# Power.net
KiCad netlist of a schematic drawn in Altium Designer
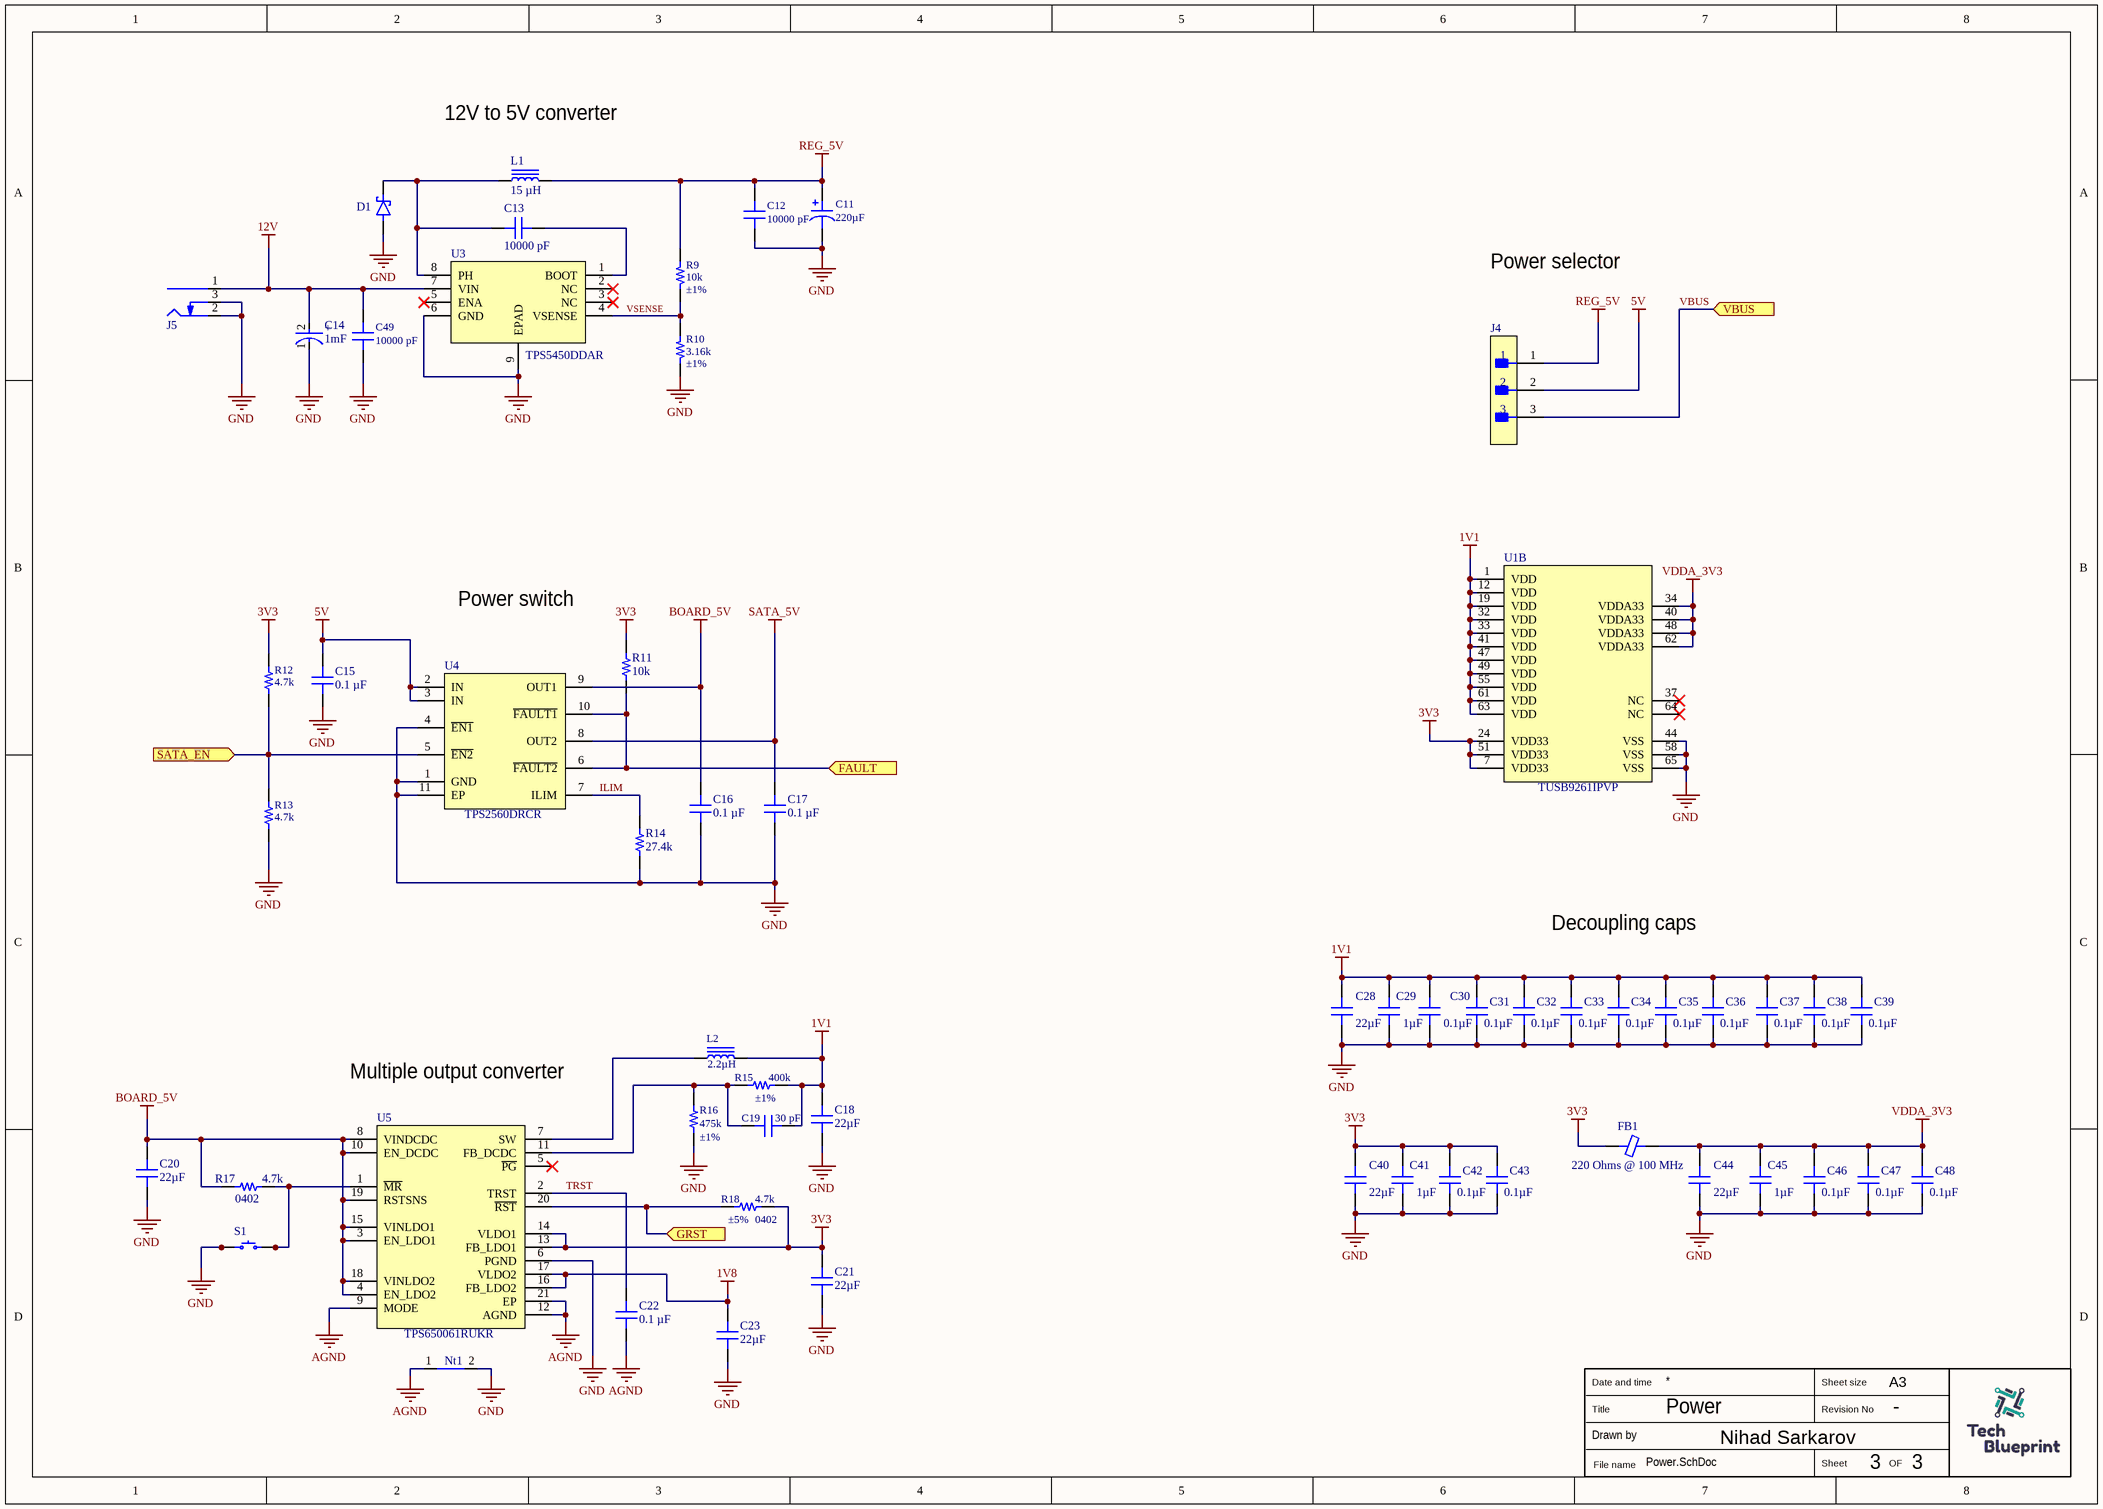
[diagram p0: Power.SchDoc]

(export (version "E")
  (design (tool "Eeschema 10.0.6"))
  (components
    (comp (ref "C11")
      (value "220µF")
      (footprint "CAP ALSMD 8.3MM H10.5MM")
      (description "CAP ALUM 220UF 20% 25V SMD")
      (fields (field (name "PART NUMBER") "UUR1E221MNL6GS") (field (name "MANUFACTURER") "Nichicon"))
      (libsource (lib "Celestial Altium Library - altium_library") (part "Polarised Capacitor"))
    )
    (comp (ref "C12")
      (value "10000 pF")
      (footprint "CAP 0805_2012")
      (description "CAP CER 0805 10NF 100V X7R")
      (fields
        (field (name "PART NUMBER") "C0805X103K1RAC3316")
        (field (name "CAPACITANCE") "10000 pF")
        (field (name "MANUFACTURER") "KEMET")
      )
      (libsource (lib "Celestial Altium Library - altium_library") (part "Capacitor"))
    )
    (comp (ref "C13")
      (value "10000 pF")
      (footprint "CAP 0805_2012")
      (description "CAP CER 0805 10NF 100V X7R")
      (fields
        (field (name "PART NUMBER") "C0805X103K1RAC3316")
        (field (name "CAPACITANCE") "10000 pF")
        (field (name "MANUFACTURER") "KEMET")
      )
      (libsource (lib "Celestial Altium Library - altium_library") (part "Capacitor"))
    )
    (comp (ref "C14")
      (value "EEEFT1C102AP")
      (footprint "FP-FTG-MFG")
      (description "CAP ALUM 1000UF 20% 16V SMD")
      (fields
        (field (name "TOLERANCE") "20%")
        (field (name "CAPACITANCE") "1mF")
        (field (name "VOLTAGE") "16V")
      )
      (libsource (lib "Altium Content Vault") (part "a00bbbee19879c290e62620ae7e47b1"))
    )
    (comp (ref "C15")
      (value "0.1 µF")
      (footprint "CAP 0603_1608")
      (description "CAP CER 0.1UF 50V X7R 0603")
      (fields
        (field (name "PART NUMBER") "CL10B104KB85PND")
        (field (name "CAPACITANCE") "0.1 µF")
        (field (name "MANUFACTURER") "Samsung Electro-Mechanics")
      )
      (libsource (lib "Celestial Altium Library - altium_library") (part "Capacitor"))
    )
    (comp (ref "C16")
      (value "0.1 µF")
      (footprint "CAP 0603_1608")
      (description "CAP CER 0.1UF 50V X7R 0603")
      (fields
        (field (name "PART NUMBER") "CL10B104KB85PND")
        (field (name "CAPACITANCE") "0.1 µF")
        (field (name "MANUFACTURER") "Samsung Electro-Mechanics")
      )
      (libsource (lib "Celestial Altium Library - altium_library") (part "Capacitor"))
    )
    (comp (ref "C17")
      (value "0.1 µF")
      (footprint "CAP 0603_1608")
      (description "CAP CER 0.1UF 50V X7R 0603")
      (fields
        (field (name "PART NUMBER") "CL10B104KB85PND")
        (field (name "CAPACITANCE") "0.1 µF")
        (field (name "MANUFACTURER") "Samsung Electro-Mechanics")
      )
      (libsource (lib "Celestial Altium Library - altium_library") (part "Capacitor"))
    )
    (comp (ref "C18")
      (value "22µF")
      (footprint "CAP 1206_3216 - 1.8MM")
      (description "CAP CER 22UF 16V X5R 1206")
      (fields
        (field (name "PART NUMBER") "1206YD226KAT2A")
        (field (name "CAPACITANCE") "22µF")
        (field (name "MANUFACTURER") "AVX Corporation")
      )
      (libsource (lib "Celestial Altium Library - altium_library") (part "Capacitor"))
    )
    (comp (ref "C19")
      (value "30 pF")
      (footprint "CAP 0402_1005")
      (description "CAP CER 30PF 50V NP0 0402")
      (fields
        (field (name "PART NUMBER") "C0402C300K5GAC7867")
        (field (name "CAPACITANCE") "30 pF")
        (field (name "MANUFACTURER") "KEMET")
      )
      (libsource (lib "Celestial Altium Library - altium_library") (part "Capacitor"))
    )
    (comp (ref "C20")
      (value "22µF")
      (footprint "CAP 1206_3216 - 1.8MM")
      (description "CAP CER 22UF 16V X5R 1206")
      (fields
        (field (name "PART NUMBER") "1206YD226KAT2A")
        (field (name "CAPACITANCE") "22µF")
        (field (name "MANUFACTURER") "AVX Corporation")
      )
      (libsource (lib "Celestial Altium Library - altium_library") (part "Capacitor"))
    )
    (comp (ref "C21")
      (value "22µF")
      (footprint "CAP 1206_3216 - 1.8MM")
      (description "CAP CER 22UF 16V X5R 1206")
      (fields
        (field (name "PART NUMBER") "1206YD226KAT2A")
        (field (name "CAPACITANCE") "22µF")
        (field (name "MANUFACTURER") "AVX Corporation")
      )
      (libsource (lib "Celestial Altium Library - altium_library") (part "Capacitor"))
    )
    (comp (ref "C22")
      (value "0.1 µF")
      (footprint "CAP 0603_1608")
      (description "CAP CER 0.1UF 50V X7R 0603")
      (fields
        (field (name "PART NUMBER") "CL10B104KB85PND")
        (field (name "CAPACITANCE") "0.1 µF")
        (field (name "MANUFACTURER") "Samsung Electro-Mechanics")
      )
      (libsource (lib "Celestial Altium Library - altium_library") (part "Capacitor"))
    )
    (comp (ref "C23")
      (value "22µF")
      (footprint "CAP 1206_3216 - 1.8MM")
      (description "CAP CER 22UF 16V X5R 1206")
      (fields
        (field (name "PART NUMBER") "1206YD226KAT2A")
        (field (name "CAPACITANCE") "22µF")
        (field (name "MANUFACTURER") "AVX Corporation")
      )
      (libsource (lib "Celestial Altium Library - altium_library") (part "Capacitor"))
    )
    (comp (ref "C28")
      (value "22µF")
      (footprint "CAP 1206_3216 - 1.8MM")
      (description "CAP CER 22UF 16V X5R 1206")
      (fields
        (field (name "PART NUMBER") "1206YD226KAT2A")
        (field (name "CAPACITANCE") "22µF")
        (field (name "MANUFACTURER") "AVX Corporation")
      )
      (libsource (lib "Celestial Altium Library - altium_library") (part "Capacitor"))
    )
    (comp (ref "C29")
      (value "1µF")
      (footprint "CAP 0805_2012")
      (description "CAP CER 1UF 10V X7R 0805")
      (fields
        (field (name "PART NUMBER") "MM05ZC105KCZ2A")
        (field (name "CAPACITANCE") "1µF")
        (field (name "MANUFACTURER") "AVX Corporation")
      )
      (libsource (lib "Celestial Altium Library - altium_library") (part "Capacitor"))
    )
    (comp (ref "C30")
      (value "0.1µF")
      (footprint "CAP 0805_2012")
      (description "CAP CER 0.1UF 25V X7R 0805")
      (fields
        (field (name "PART NUMBER") "08053C104KAT4A")
        (field (name "CAPACITANCE") "0.1µF")
        (field (name "MANUFACTURER") "AVX Corporation")
      )
      (libsource (lib "Celestial Altium Library - altium_library") (part "Capacitor"))
    )
    (comp (ref "C31")
      (value "0.1µF")
      (footprint "CAP 0603_1608")
      (description "CAP CER 0.1UF 25V X7R 0603")
      (fields
        (field (name "PART NUMBER") "06033C104K4T4A")
        (field (name "CAPACITANCE") "0.1µF")
        (field (name "MANUFACTURER") "AVX Corporation")
      )
      (libsource (lib "Celestial Altium Library - altium_library") (part "Capacitor"))
    )
    (comp (ref "C32")
      (value "0.1µF")
      (footprint "CAP 0603_1608")
      (description "CAP CER 0.1UF 25V X7R 0603")
      (fields
        (field (name "PART NUMBER") "06033C104K4T4A")
        (field (name "CAPACITANCE") "0.1µF")
        (field (name "MANUFACTURER") "AVX Corporation")
      )
      (libsource (lib "Celestial Altium Library - altium_library") (part "Capacitor"))
    )
    (comp (ref "C33")
      (value "0.1µF")
      (footprint "CAP 0603_1608")
      (description "CAP CER 0.1UF 25V X7R 0603")
      (fields
        (field (name "PART NUMBER") "06033C104K4T4A")
        (field (name "CAPACITANCE") "0.1µF")
        (field (name "MANUFACTURER") "AVX Corporation")
      )
      (libsource (lib "Celestial Altium Library - altium_library") (part "Capacitor"))
    )
    (comp (ref "C34")
      (value "0.1µF")
      (footprint "CAP 0603_1608")
      (description "CAP CER 0.1UF 25V X7R 0603")
      (fields
        (field (name "PART NUMBER") "06033C104K4T4A")
        (field (name "CAPACITANCE") "0.1µF")
        (field (name "MANUFACTURER") "AVX Corporation")
      )
      (libsource (lib "Celestial Altium Library - altium_library") (part "Capacitor"))
    )
    (comp (ref "C35")
      (value "0.1µF")
      (footprint "CAP 0603_1608")
      (description "CAP CER 0.1UF 25V X7R 0603")
      (fields
        (field (name "PART NUMBER") "06033C104K4T4A")
        (field (name "CAPACITANCE") "0.1µF")
        (field (name "MANUFACTURER") "AVX Corporation")
      )
      (libsource (lib "Celestial Altium Library - altium_library") (part "Capacitor"))
    )
    (comp (ref "C36")
      (value "0.1µF")
      (footprint "CAP 0603_1608")
      (description "CAP CER 0.1UF 25V X7R 0603")
      (fields
        (field (name "PART NUMBER") "06033C104K4T4A")
        (field (name "CAPACITANCE") "0.1µF")
        (field (name "MANUFACTURER") "AVX Corporation")
      )
      (libsource (lib "Celestial Altium Library - altium_library") (part "Capacitor"))
    )
    (comp (ref "C37")
      (value "0.1µF")
      (footprint "CAP 0603_1608")
      (description "CAP CER 0.1UF 25V X7R 0603")
      (fields
        (field (name "PART NUMBER") "06033C104K4T4A")
        (field (name "CAPACITANCE") "0.1µF")
        (field (name "MANUFACTURER") "AVX Corporation")
      )
      (libsource (lib "Celestial Altium Library - altium_library") (part "Capacitor"))
    )
    (comp (ref "C38")
      (value "0.1µF")
      (footprint "CAP 0603_1608")
      (description "CAP CER 0.1UF 25V X7R 0603")
      (fields
        (field (name "PART NUMBER") "06033C104K4T4A")
        (field (name "CAPACITANCE") "0.1µF")
        (field (name "MANUFACTURER") "AVX Corporation")
      )
      (libsource (lib "Celestial Altium Library - altium_library") (part "Capacitor"))
    )
    (comp (ref "C39")
      (value "0.1µF")
      (footprint "CAP 0603_1608")
      (description "CAP CER 0.1UF 25V X7R 0603")
      (fields
        (field (name "PART NUMBER") "06033C104K4T4A")
        (field (name "CAPACITANCE") "0.1µF")
        (field (name "MANUFACTURER") "AVX Corporation")
      )
      (libsource (lib "Celestial Altium Library - altium_library") (part "Capacitor"))
    )
    (comp (ref "C40")
      (value "22µF")
      (footprint "CAP 1206_3216 - 1.8MM")
      (description "CAP CER 22UF 16V X5R 1206")
      (fields
        (field (name "PART NUMBER") "1206YD226KAT2A")
        (field (name "CAPACITANCE") "22µF")
        (field (name "MANUFACTURER") "AVX Corporation")
      )
      (libsource (lib "Celestial Altium Library - altium_library") (part "Capacitor"))
    )
    (comp (ref "C41")
      (value "1µF")
      (footprint "CAP 0805_2012")
      (description "CAP CER 1UF 10V X7R 0805")
      (fields
        (field (name "PART NUMBER") "MM05ZC105KCZ2A")
        (field (name "CAPACITANCE") "1µF")
        (field (name "MANUFACTURER") "AVX Corporation")
      )
      (libsource (lib "Celestial Altium Library - altium_library") (part "Capacitor"))
    )
    (comp (ref "C42")
      (value "0.1µF")
      (footprint "CAP 0603_1608")
      (description "CAP CER 0.1UF 25V X7R 0603")
      (fields
        (field (name "PART NUMBER") "06033C104K4T4A")
        (field (name "CAPACITANCE") "0.1µF")
        (field (name "MANUFACTURER") "AVX Corporation")
      )
      (libsource (lib "Celestial Altium Library - altium_library") (part "Capacitor"))
    )
    (comp (ref "C43")
      (value "0.1µF")
      (footprint "CAP 0603_1608")
      (description "CAP CER 0.1UF 25V X7R 0603")
      (fields
        (field (name "PART NUMBER") "06033C104K4T4A")
        (field (name "CAPACITANCE") "0.1µF")
        (field (name "MANUFACTURER") "AVX Corporation")
      )
      (libsource (lib "Celestial Altium Library - altium_library") (part "Capacitor"))
    )
    (comp (ref "C44")
      (value "22µF")
      (footprint "CAP 1206_3216 - 1.8MM")
      (description "CAP CER 22UF 16V X5R 1206")
      (fields
        (field (name "PART NUMBER") "1206YD226KAT2A")
        (field (name "CAPACITANCE") "22µF")
        (field (name "MANUFACTURER") "AVX Corporation")
      )
      (libsource (lib "Celestial Altium Library - altium_library") (part "Capacitor"))
    )
    (comp (ref "C45")
      (value "1µF")
      (footprint "CAP 0805_2012")
      (description "CAP CER 1UF 10V X7R 0805")
      (fields
        (field (name "PART NUMBER") "MM05ZC105KCZ2A")
        (field (name "CAPACITANCE") "1µF")
        (field (name "MANUFACTURER") "AVX Corporation")
      )
      (libsource (lib "Celestial Altium Library - altium_library") (part "Capacitor"))
    )
    (comp (ref "C46")
      (value "0.1µF")
      (footprint "CAP 0603_1608")
      (description "CAP CER 0.1UF 25V X7R 0603")
      (fields
        (field (name "PART NUMBER") "06033C104K4T4A")
        (field (name "CAPACITANCE") "0.1µF")
        (field (name "MANUFACTURER") "AVX Corporation")
      )
      (libsource (lib "Celestial Altium Library - altium_library") (part "Capacitor"))
    )
    (comp (ref "C47")
      (value "0.1µF")
      (footprint "CAP 0603_1608")
      (description "CAP CER 0.1UF 25V X7R 0603")
      (fields
        (field (name "PART NUMBER") "06033C104K4T4A")
        (field (name "CAPACITANCE") "0.1µF")
        (field (name "MANUFACTURER") "AVX Corporation")
      )
      (libsource (lib "Celestial Altium Library - altium_library") (part "Capacitor"))
    )
    (comp (ref "C48")
      (value "0.1µF")
      (footprint "CAP 0603_1608")
      (description "CAP CER 0.1UF 25V X7R 0603")
      (fields
        (field (name "PART NUMBER") "06033C104K4T4A")
        (field (name "CAPACITANCE") "0.1µF")
        (field (name "MANUFACTURER") "AVX Corporation")
      )
      (libsource (lib "Celestial Altium Library - altium_library") (part "Capacitor"))
    )
    (comp (ref "C49")
      (value "10000 pF")
      (footprint "CAP 0805_2012")
      (description "CAP CER 0805 10NF 100V X7R")
      (fields
        (field (name "PART NUMBER") "C0805X103K1RAC3316")
        (field (name "CAPACITANCE") "10000 pF")
        (field (name "MANUFACTURER") "KEMET")
      )
      (libsource (lib "Celestial Altium Library - altium_library") (part "Capacitor"))
    )
    (comp (ref "D1")
      (value "MBRS540T3G")
      (footprint "MBRS540T3G:DIOM7959X261N")
      (fields (field (name "MF") "{'manufacturer': u'ON Semiconductor'}"))
      (libsource (lib "USB to SATA") (part "MBRS540T3G"))
    )
    (comp (ref "FB1")
      (value "220 Ohms @ 100 MHz")
      (footprint "FER 0603_1608")
      (description "POWER LINE HIGH IMPEDANCE FERRIT")
      (fields (field (name "PART NUMBER") "Z0603C221BPWZT") (field (name "MANUFACTURER") "KEMET"))
      (libsource (lib "Celestial Altium Library - altium_library") (part "Ferrite Chip"))
    )
    (comp (ref "J4")
      (value "87224-3")
      (footprint "FP-87224-3-MFG")
      (description "CONN HEADER VERT 3POS 2.54MM")
      (libsource (lib "USB to SATA") (part "CMP-2000-05697-2"))
    )
    (comp (ref "J5")
      (value "PJ-002AH-SMT-TR")
      (footprint "CUI PJ-002AH-SMT-TR")
      (description "CONN PWR JACK 2X5.5MM SOLDER")
      (fields (field (name "MANUFACTURER") "CUI Devices"))
      (libsource (lib "Celestial Altium Library - altium_library") (part "Barrel Connector"))
    )
    (comp (ref "L1")
      (value "15 µH")
      (footprint "BOURNS SRR1280")
      (description "FIXED IND 15UH 5.2A 28.5MOHM SMD")
      (fields (field (name "PART NUMBER") "SRR1280-150M") (field (name "MANUFACTURER") "Bourns Inc."))
      (libsource (lib "") (part "Inductor_1"))
    )
    (comp (ref "L2")
      (value "2.2µH")
      (footprint "IND 1008_2520")
      (description "FIXED IND 2.2UH 700MA 150 MOHM")
      (fields (field (name "PART NUMBER") "CKP2520V2R2M-T") (field (name "MANUFACTURER") "Taiyo Yuden"))
      (libsource (lib "Celestial Altium Library - altium_library") (part "Inductor"))
    )
    (comp (ref "Nt1")
      (value "Net tie")
      (footprint "Net tie")
      (description "Net tie SMD")
      (libsource (lib "USB to SATA") (part "Net tie"))
    )
    (comp (ref "R9")
      (value "10k")
      (footprint "YAGEO RES 0603_1608")
      (description "RES SMD 10K OHM 1% 1/10W 0603")
      (fields
        (field (name "PART NUMBER") "RT0603FRE0710KL")
        (field (name "MANUFACTURER") "Yageo")
        (field (name "TOLERANCE") "±1%")
      )
      (libsource (lib "Celestial Altium Library - altium_library") (part "Resistor"))
    )
    (comp (ref "R10")
      (value "3.16k")
      (footprint "RES 0603_1608")
      (description "RES SMD 3.16K OHM 1% 1/10W 0603")
      (fields
        (field (name "PART NUMBER") "CR0603-FX-3161ELF")
        (field (name "MANUFACTURER") "Bourns Inc.")
        (field (name "TOLERANCE") "±1%")
      )
      (libsource (lib "Celestial Altium Library - altium_library") (part "Resistor"))
    )
    (comp (ref "R11")
      (value "10k")
      (footprint "YAGEO RES 0402_1005")
      (description "RES SMD 10K OHM 5% 1/16W 0402")
      (fields (field (name "PART NUMBER") "AC0402JR-0710KL") (field (name "MANUFACTURER") "Yageo"))
      (libsource (lib "Celestial Altium Library - altium_library") (part "Resistor"))
    )
    (comp (ref "R12")
      (value "4.7k")
      (footprint "RES 0603_1608")
      (description "RES 4.7K OHM 5% 1/10W 0603")
      (fields
        (field (name "PART NUMBER") "RMCF0603JT4K70")
        (field (name "MANUFACTURER") "Stackpole Electronics Inc")
      )
      (libsource (lib "Celestial Altium Library - altium_library") (part "Resistor"))
    )
    (comp (ref "R13")
      (value "4.7k")
      (footprint "RES 0603_1608")
      (description "RES 4.7K OHM 5% 1/10W 0603")
      (fields
        (field (name "PART NUMBER") "RMCF0603JT4K70")
        (field (name "MANUFACTURER") "Stackpole Electronics Inc")
      )
      (libsource (lib "Celestial Altium Library - altium_library") (part "Resistor"))
    )
    (comp (ref "R14")
      (value "27.4k")
      (footprint "RES 0402_1005")
      (description "RES SMD 27.4K OHM 1% 1/10W 0402")
      (fields
        (field (name "PART NUMBER") "ERJ-2RKF2742X")
        (field (name "MANUFACTURER") "Panasonic Electronic Components")
      )
      (libsource (lib "Celestial Altium Library - altium_library") (part "Resistor"))
    )
    (comp (ref "R15")
      (value "400k")
      (footprint "KOA RES RK73 RN73 0402_1005")
      (description "RES 400K OHM 1% 1/10W 0402")
      (fields
        (field (name "PART NUMBER") "RK73H1ETTP4123F")
        (field (name "MANUFACTURER") "KOA Speer Electronics, Inc.")
        (field (name "TOLERANCE") "±1%")
      )
      (libsource (lib "Celestial Altium Library - altium_library") (part "Resistor"))
    )
    (comp (ref "R16")
      (value "475k")
      (footprint "RES 0402_1005")
      (description "RES 475K OHM 1% 1/16W 0402")
      (fields
        (field (name "PART NUMBER") "RMCF0402FT475K")
        (field (name "MANUFACTURER") "Stackpole Electronics Inc")
        (field (name "TOLERANCE") "±1%")
      )
      (libsource (lib "Celestial Altium Library - altium_library") (part "Resistor"))
    )
    (comp (ref "R17")
      (value "4.7k")
      (footprint "YAGEO RES 0402_1005")
      (description "RES SMD 4.7K OHM 5% 1/16W 0402")
      (fields
        (field (name "PART NUMBER") "AC0402JR-074K7L")
        (field (name "MANUFACTURER") "Yageo")
        (field (name "SUPPLIER DEVICE PACKAGE") "0402")
      )
      (libsource (lib "Celestial Altium Library - altium_library") (part "Resistor"))
    )
    (comp (ref "R18")
      (value "4.7k")
      (footprint "YAGEO RES 0402_1005")
      (description "RES SMD 4.7K OHM 5% 1/16W 0402")
      (fields
        (field (name "PART NUMBER") "AC0402JR-074K7L")
        (field (name "MANUFACTURER") "Yageo")
        (field (name "SUPPLIER DEVICE PACKAGE") "0402")
        (field (name "TOLERANCE") "±5%")
      )
      (libsource (lib "Celestial Altium Library - altium_library") (part "Resistor"))
    )
    (comp (ref "S1")
      (value "PTS645SM43SMTR92 LFS")
      (footprint "C&K PTS645")
      (description "SWITCH TACTILE SPST-NO 0.05A 12V")
      (fields (field (name "MANUFACTURER") "C&K"))
      (libsource (lib "Celestial Altium Library - altium_library") (part "SPST-NO 4 PIN"))
    )
    (comp (ref "U1")
      (value "TUSB9261IPVP")
      (footprint "FP-PVP0064A-IPC_A")
      (description "HDD, CD, DVD Drive Interface 64-HTQFP (7x7)")
      (fields
        (field (name "MANUFACTURER") "Texas Instruments")
        (field (name "DIGIKEY PART NUMBER") "296-35545-ND")
      )
      (libsource (lib "USB to SATA") (part "TUSB9261IPVP"))
    )
    (comp (ref "U3")
      (value "TPS5450DDAR")
      (footprint "FP-DDA0008J-IPC_A")
      (description "IC REG BUCK ADJUSTABLE 5A 8SOPWR")
      (fields
        (field (name "MANUFACTURER") "Texas Instruments")
        (field (name "OCTOPART") "https://octopart.com/tps5450ddar-texas+instruments-7105511")
      )
      (libsource (lib "USB to SATA") (part "CMP-04918-000100-1"))
    )
    (comp (ref "U4")
      (value "TPS2560DRCR")
      (footprint "FP-DRC0010J-IPC_A")
      (description "IC PWR SWITCH N-CHAN 1:2 10VSON")
      (libsource (lib "USB to SATA") (part "CMP-0337-00200-3"))
    )
    (comp (ref "U5")
      (value "TPS650061RUKR")
      (footprint "RUK0020B")
      (fields (field (name "MANUFACTURER") "Texas Instruments"))
      (libsource (lib "USB to SATA") (part "CMP-1518-00013-2"))
    )
  )
  (nets
    (net (code "1") (name "/FAULT") (class "Default")
      (node (ref "R11") (pin "1") (pinfunction "1_1") (pintype "passive"))
      (node (ref "U4") (pin "10") (pinfunction "~{FAULT1}_10") (pintype "passive"))
      (node (ref "U4") (pin "6") (pinfunction "~{FAULT2}_6") (pintype "passive"))
    )
    (net (code "2") (name "/GRST") (class "Default")
      (node (ref "R18") (pin "1") (pinfunction "1_1") (pintype "passive"))
      (node (ref "U5") (pin "20") (pinfunction "~{RST}_20") (pintype "passive"))
    )
    (net (code "3") (name "/ILIM") (class "Default")
      (node (ref "R14") (pin "2") (pinfunction "2_2") (pintype "passive"))
      (node (ref "U4") (pin "7") (pinfunction "ILIM_7") (pintype "passive"))
    )
    (net (code "4") (name "/SATA_EN") (class "Default")
      (node (ref "R12") (pin "1") (pinfunction "1_1") (pintype "passive"))
      (node (ref "R13") (pin "2") (pinfunction "2_2") (pintype "passive"))
      (node (ref "U4") (pin "5") (pinfunction "~{EN2}_5") (pintype "passive"))
    )
    (net (code "5") (name "/TRST") (class "Default")
      (node (ref "C22") (pin "2") (pinfunction "2_2") (pintype "passive"))
      (node (ref "U5") (pin "2") (pinfunction "TRST_2") (pintype "passive"))
    )
    (net (code "6") (name "/VBUS") (class "Default")
      (node (ref "J4") (pin "3") (pinfunction "3_3") (pintype "passive"))
    )
    (net (code "7") (name "/VSENSE") (class "Default")
      (node (ref "R10") (pin "2") (pinfunction "2_2") (pintype "passive"))
      (node (ref "R9") (pin "1") (pinfunction "1_1") (pintype "passive"))
      (node (ref "U3") (pin "4") (pinfunction "VSENSE_4") (pintype "passive"))
    )
    (net (code "8") (name "1V1") (class "Default")
      (node (ref "C18") (pin "2") (pinfunction "2_2") (pintype "passive"))
      (node (ref "C19") (pin "2") (pinfunction "2_2") (pintype "passive"))
      (node (ref "C28") (pin "2") (pinfunction "2_2") (pintype "passive"))
      (node (ref "C29") (pin "2") (pinfunction "2_2") (pintype "passive"))
      (node (ref "C30") (pin "2") (pinfunction "2_2") (pintype "passive"))
      (node (ref "C31") (pin "2") (pinfunction "2_2") (pintype "passive"))
      (node (ref "C32") (pin "2") (pinfunction "2_2") (pintype "passive"))
      (node (ref "C33") (pin "2") (pinfunction "2_2") (pintype "passive"))
      (node (ref "C34") (pin "2") (pinfunction "2_2") (pintype "passive"))
      (node (ref "C35") (pin "2") (pinfunction "2_2") (pintype "passive"))
      (node (ref "C36") (pin "2") (pinfunction "2_2") (pintype "passive"))
      (node (ref "C37") (pin "2") (pinfunction "2_2") (pintype "passive"))
      (node (ref "C38") (pin "2") (pinfunction "2_2") (pintype "passive"))
      (node (ref "C39") (pin "2") (pinfunction "2_2") (pintype "passive"))
      (node (ref "L2") (pin "2") (pinfunction "2_2") (pintype "passive"))
      (node (ref "R15") (pin "2") (pinfunction "2_2") (pintype "passive"))
      (node (ref "U1") (pin "1") (pinfunction "VDD_1") (pintype "passive"))
      (node (ref "U1") (pin "12") (pinfunction "VDD_12") (pintype "passive"))
      (node (ref "U1") (pin "19") (pinfunction "VDD_19") (pintype "passive"))
      (node (ref "U1") (pin "32") (pinfunction "VDD_32") (pintype "passive"))
      (node (ref "U1") (pin "33") (pinfunction "VDD_33") (pintype "passive"))
      (node (ref "U1") (pin "41") (pinfunction "VDD_41") (pintype "passive"))
      (node (ref "U1") (pin "47") (pinfunction "VDD_47") (pintype "passive"))
      (node (ref "U1") (pin "49") (pinfunction "VDD_49") (pintype "passive"))
      (node (ref "U1") (pin "55") (pinfunction "VDD_55") (pintype "passive"))
      (node (ref "U1") (pin "61") (pinfunction "VDD_61") (pintype "passive"))
      (node (ref "U1") (pin "63") (pinfunction "VDD_63") (pintype "passive"))
    )
    (net (code "9") (name "1V8") (class "Default")
      (node (ref "C23") (pin "2") (pinfunction "2_2") (pintype "passive"))
      (node (ref "U5") (pin "16") (pinfunction "FB_LDO2_16") (pintype "passive"))
      (node (ref "U5") (pin "17") (pinfunction "VLDO2_17") (pintype "passive"))
    )
    (net (code "10") (name "3V3") (class "Default")
      (node (ref "C21") (pin "2") (pinfunction "2_2") (pintype "passive"))
      (node (ref "C40") (pin "2") (pinfunction "2_2") (pintype "passive"))
      (node (ref "C41") (pin "2") (pinfunction "2_2") (pintype "passive"))
      (node (ref "C42") (pin "2") (pinfunction "2_2") (pintype "passive"))
      (node (ref "C43") (pin "2") (pinfunction "2_2") (pintype "passive"))
      (node (ref "FB1") (pin "1") (pinfunction "1_1") (pintype "passive"))
      (node (ref "R11") (pin "2") (pinfunction "2_2") (pintype "passive"))
      (node (ref "R12") (pin "2") (pinfunction "2_2") (pintype "passive"))
      (node (ref "R18") (pin "2") (pinfunction "2_2") (pintype "passive"))
      (node (ref "U1") (pin "24") (pinfunction "VDD33_24") (pintype "passive"))
      (node (ref "U1") (pin "51") (pinfunction "VDD33_51") (pintype "passive"))
      (node (ref "U1") (pin "7") (pinfunction "VDD33_7") (pintype "passive"))
      (node (ref "U5") (pin "13") (pinfunction "FB_LDO1_13") (pintype "passive"))
      (node (ref "U5") (pin "14") (pinfunction "VLDO1_14") (pintype "passive"))
    )
    (net (code "11") (name "5V") (class "Default")
      (node (ref "C15") (pin "2") (pinfunction "2_2") (pintype "passive"))
      (node (ref "J4") (pin "2") (pinfunction "2_2") (pintype "passive"))
      (node (ref "U4") (pin "2") (pinfunction "IN_2") (pintype "power_in"))
      (node (ref "U4") (pin "3") (pinfunction "IN_3") (pintype "power_in"))
    )
    (net (code "12") (name "12V") (class "Default")
      (node (ref "C14") (pin "2") (pinfunction "A_2") (pintype "passive"))
      (node (ref "C49") (pin "2") (pinfunction "2_2") (pintype "passive"))
      (node (ref "J5") (pin "1") (pinfunction "Centre_1") (pintype "passive"))
      (node (ref "U3") (pin "7") (pinfunction "VIN_7") (pintype "passive"))
    )
    (net (code "13") (name "AGND") (class "Default")
      (node (ref "C22") (pin "1") (pinfunction "1_1") (pintype "passive"))
      (node (ref "Nt1") (pin "1") (pinfunction "1_1") (pintype "passive"))
      (node (ref "U5") (pin "12") (pinfunction "AGND_12") (pintype "passive"))
      (node (ref "U5") (pin "21") (pinfunction "EP_21") (pintype "passive"))
      (node (ref "U5") (pin "9") (pinfunction "MODE_9") (pintype "passive"))
    )
    (net (code "14") (name "BOARD_5V") (class "Default")
      (node (ref "C16") (pin "2") (pinfunction "2_2") (pintype "passive"))
      (node (ref "C20") (pin "2") (pinfunction "2_2") (pintype "passive"))
      (node (ref "R17") (pin "1") (pinfunction "1_1") (pintype "passive"))
      (node (ref "U4") (pin "9") (pinfunction "OUT1_9") (pintype "passive"))
      (node (ref "U5") (pin "10") (pinfunction "EN_DCDC_10") (pintype "passive"))
      (node (ref "U5") (pin "15") (pinfunction "VINLDO1_15") (pintype "passive"))
      (node (ref "U5") (pin "18") (pinfunction "VINLDO2_18") (pintype "passive"))
      (node (ref "U5") (pin "19") (pinfunction "RSTSNS_19") (pintype "passive"))
      (node (ref "U5") (pin "3") (pinfunction "EN_LDO1_3") (pintype "passive"))
      (node (ref "U5") (pin "4") (pinfunction "EN_LDO2_4") (pintype "passive"))
      (node (ref "U5") (pin "8") (pinfunction "VINDCDC_8") (pintype "passive"))
    )
    (net (code "15") (name "GND") (class "Default")
      (node (ref "C11") (pin "2") (pinfunction "2_2") (pintype "passive"))
      (node (ref "C12") (pin "1") (pinfunction "1_1") (pintype "passive"))
      (node (ref "C14") (pin "1") (pinfunction "C_1") (pintype "passive"))
      (node (ref "C15") (pin "1") (pinfunction "1_1") (pintype "passive"))
      (node (ref "C16") (pin "1") (pinfunction "1_1") (pintype "passive"))
      (node (ref "C17") (pin "1") (pinfunction "1_1") (pintype "passive"))
      (node (ref "C18") (pin "1") (pinfunction "1_1") (pintype "passive"))
      (node (ref "C20") (pin "1") (pinfunction "1_1") (pintype "passive"))
      (node (ref "C21") (pin "1") (pinfunction "1_1") (pintype "passive"))
      (node (ref "C23") (pin "1") (pinfunction "1_1") (pintype "passive"))
      (node (ref "C28") (pin "1") (pinfunction "1_1") (pintype "passive"))
      (node (ref "C29") (pin "1") (pinfunction "1_1") (pintype "passive"))
      (node (ref "C30") (pin "1") (pinfunction "1_1") (pintype "passive"))
      (node (ref "C31") (pin "1") (pinfunction "1_1") (pintype "passive"))
      (node (ref "C32") (pin "1") (pinfunction "1_1") (pintype "passive"))
      (node (ref "C33") (pin "1") (pinfunction "1_1") (pintype "passive"))
      (node (ref "C34") (pin "1") (pinfunction "1_1") (pintype "passive"))
      (node (ref "C35") (pin "1") (pinfunction "1_1") (pintype "passive"))
      (node (ref "C36") (pin "1") (pinfunction "1_1") (pintype "passive"))
      (node (ref "C37") (pin "1") (pinfunction "1_1") (pintype "passive"))
      (node (ref "C38") (pin "1") (pinfunction "1_1") (pintype "passive"))
      (node (ref "C39") (pin "1") (pinfunction "1_1") (pintype "passive"))
      (node (ref "C40") (pin "1") (pinfunction "1_1") (pintype "passive"))
      (node (ref "C41") (pin "1") (pinfunction "1_1") (pintype "passive"))
      (node (ref "C42") (pin "1") (pinfunction "1_1") (pintype "passive"))
      (node (ref "C43") (pin "1") (pinfunction "1_1") (pintype "passive"))
      (node (ref "C44") (pin "1") (pinfunction "1_1") (pintype "passive"))
      (node (ref "C45") (pin "1") (pinfunction "1_1") (pintype "passive"))
      (node (ref "C46") (pin "1") (pinfunction "1_1") (pintype "passive"))
      (node (ref "C47") (pin "1") (pinfunction "1_1") (pintype "passive"))
      (node (ref "C48") (pin "1") (pinfunction "1_1") (pintype "passive"))
      (node (ref "C49") (pin "1") (pinfunction "1_1") (pintype "passive"))
      (node (ref "D1") (pin "2") (pinfunction "A_2") (pintype "passive"))
      (node (ref "J5") (pin "2") (pinfunction "Outer_2") (pintype "passive"))
      (node (ref "J5") (pin "3") (pinfunction "SW_3") (pintype "passive"))
      (node (ref "Nt1") (pin "2") (pinfunction "2_2") (pintype "passive"))
      (node (ref "R10") (pin "1") (pinfunction "1_1") (pintype "passive"))
      (node (ref "R13") (pin "1") (pinfunction "1_1") (pintype "passive"))
      (node (ref "R14") (pin "1") (pinfunction "1_1") (pintype "passive"))
      (node (ref "R16") (pin "1") (pinfunction "1_1") (pintype "passive"))
      (node (ref "S1") (pin "1") (pinfunction "1_1") (pintype "passive"))
      (node (ref "S1") (pin "2") (pinfunction "2_2") (pintype "passive"))
      (node (ref "U1") (pin "44") (pinfunction "VSS_44") (pintype "passive"))
      (node (ref "U1") (pin "58") (pinfunction "VSS_58") (pintype "passive"))
      (node (ref "U1") (pin "65") (pinfunction "VSS_65") (pintype "passive"))
      (node (ref "U3") (pin "6") (pinfunction "GND_6") (pintype "passive"))
      (node (ref "U3") (pin "9") (pinfunction "EPAD_9") (pintype "power_in"))
      (node (ref "U4") (pin "1") (pinfunction "GND_1") (pintype "passive"))
      (node (ref "U4") (pin "11") (pinfunction "EP_11") (pintype "passive"))
      (node (ref "U4") (pin "4") (pinfunction "~{EN1}_4") (pintype "passive"))
      (node (ref "U5") (pin "6") (pinfunction "PGND_6") (pintype "passive"))
    )
    (net (code "16") (name "Net-(D1-C)") (class "Default")
      (node (ref "C13") (pin "1") (pinfunction "1_1") (pintype "passive"))
      (node (ref "D1") (pin "1") (pinfunction "C_1") (pintype "passive"))
      (node (ref "L1") (pin "2") (pinfunction "2_2") (pintype "passive"))
      (node (ref "U3") (pin "8") (pinfunction "PH_8") (pintype "passive"))
    )
    (net (code "17") (name "Net-(U3-BOOT)") (class "Default")
      (node (ref "C13") (pin "2") (pinfunction "2_2") (pintype "passive"))
      (node (ref "U3") (pin "1") (pinfunction "BOOT_1") (pintype "passive"))
    )
    (net (code "18") (name "Net-(U5-FB_DCDC)") (class "Default")
      (node (ref "C19") (pin "1") (pinfunction "1_1") (pintype "passive"))
      (node (ref "R15") (pin "1") (pinfunction "1_1") (pintype "passive"))
      (node (ref "R16") (pin "2") (pinfunction "2_2") (pintype "passive"))
      (node (ref "U5") (pin "11") (pinfunction "FB_DCDC_11") (pintype "passive"))
    )
    (net (code "19") (name "Net-(U5-SW)") (class "Default")
      (node (ref "L2") (pin "1") (pinfunction "1_1") (pintype "passive"))
      (node (ref "U5") (pin "7") (pinfunction "SW_7") (pintype "passive"))
    )
    (net (code "20") (name "Net-(U5-~{MR})") (class "Default")
      (node (ref "R17") (pin "2") (pinfunction "2_2") (pintype "passive"))
      (node (ref "S1") (pin "3") (pinfunction "3_3") (pintype "passive"))
      (node (ref "S1") (pin "4") (pinfunction "4_4") (pintype "passive"))
      (node (ref "U5") (pin "1") (pinfunction "~{MR}_1") (pintype "passive"))
    )
    (net (code "21") (name "REG_5V") (class "Default")
      (node (ref "C11") (pin "1") (pinfunction "1_1") (pintype "passive"))
      (node (ref "C12") (pin "2") (pinfunction "2_2") (pintype "passive"))
      (node (ref "J4") (pin "1") (pinfunction "1_1") (pintype "passive"))
      (node (ref "L1") (pin "1") (pinfunction "1_1") (pintype "passive"))
      (node (ref "R9") (pin "2") (pinfunction "2_2") (pintype "passive"))
    )
    (net (code "22") (name "SATA_5V") (class "Default")
      (node (ref "C17") (pin "2") (pinfunction "2_2") (pintype "passive"))
      (node (ref "U4") (pin "8") (pinfunction "OUT2_8") (pintype "passive"))
    )
    (net (code "23") (name "VDDA_3V3") (class "Default")
      (node (ref "C44") (pin "2") (pinfunction "2_2") (pintype "passive"))
      (node (ref "C45") (pin "2") (pinfunction "2_2") (pintype "passive"))
      (node (ref "C46") (pin "2") (pinfunction "2_2") (pintype "passive"))
      (node (ref "C47") (pin "2") (pinfunction "2_2") (pintype "passive"))
      (node (ref "C48") (pin "2") (pinfunction "2_2") (pintype "passive"))
      (node (ref "FB1") (pin "2") (pinfunction "2_2") (pintype "passive"))
      (node (ref "U1") (pin "34") (pinfunction "VDDA33_34") (pintype "passive"))
      (node (ref "U1") (pin "40") (pinfunction "VDDA33_40") (pintype "passive"))
      (node (ref "U1") (pin "48") (pinfunction "VDDA33_48") (pintype "passive"))
      (node (ref "U1") (pin "62") (pinfunction "VDDA33_62") (pintype "passive"))
    )
    (net (code "24") (name "unconnected-(U1B-NC-Pad37)") (class "Default")
      (node (ref "U1") (pin "37") (pinfunction "NC_37") (pintype "passive+no_connect"))
    )
    (net (code "25") (name "unconnected-(U1B-NC-Pad64)") (class "Default")
      (node (ref "U1") (pin "64") (pinfunction "NC_64") (pintype "passive+no_connect"))
    )
    (net (code "26") (name "unconnected-(U3-ENA-Pad5)") (class "Default")
      (node (ref "U3") (pin "5") (pinfunction "ENA_5") (pintype "passive+no_connect"))
    )
    (net (code "27") (name "unconnected-(U3-NC-Pad2)") (class "Default")
      (node (ref "U3") (pin "2") (pinfunction "NC_2") (pintype "passive+no_connect"))
    )
    (net (code "28") (name "unconnected-(U3-NC-Pad3)") (class "Default")
      (node (ref "U3") (pin "3") (pinfunction "NC_3") (pintype "passive+no_connect"))
    )
    (net (code "29") (name "unconnected-(U5-~{PG}-Pad5)") (class "Default")
      (node (ref "U5") (pin "5") (pinfunction "~{PG}_5") (pintype "passive+no_connect"))
    )
  )
)
